# EARM01_Rev_B.net
KiCad netlist of a schematic drawn in EAGLE
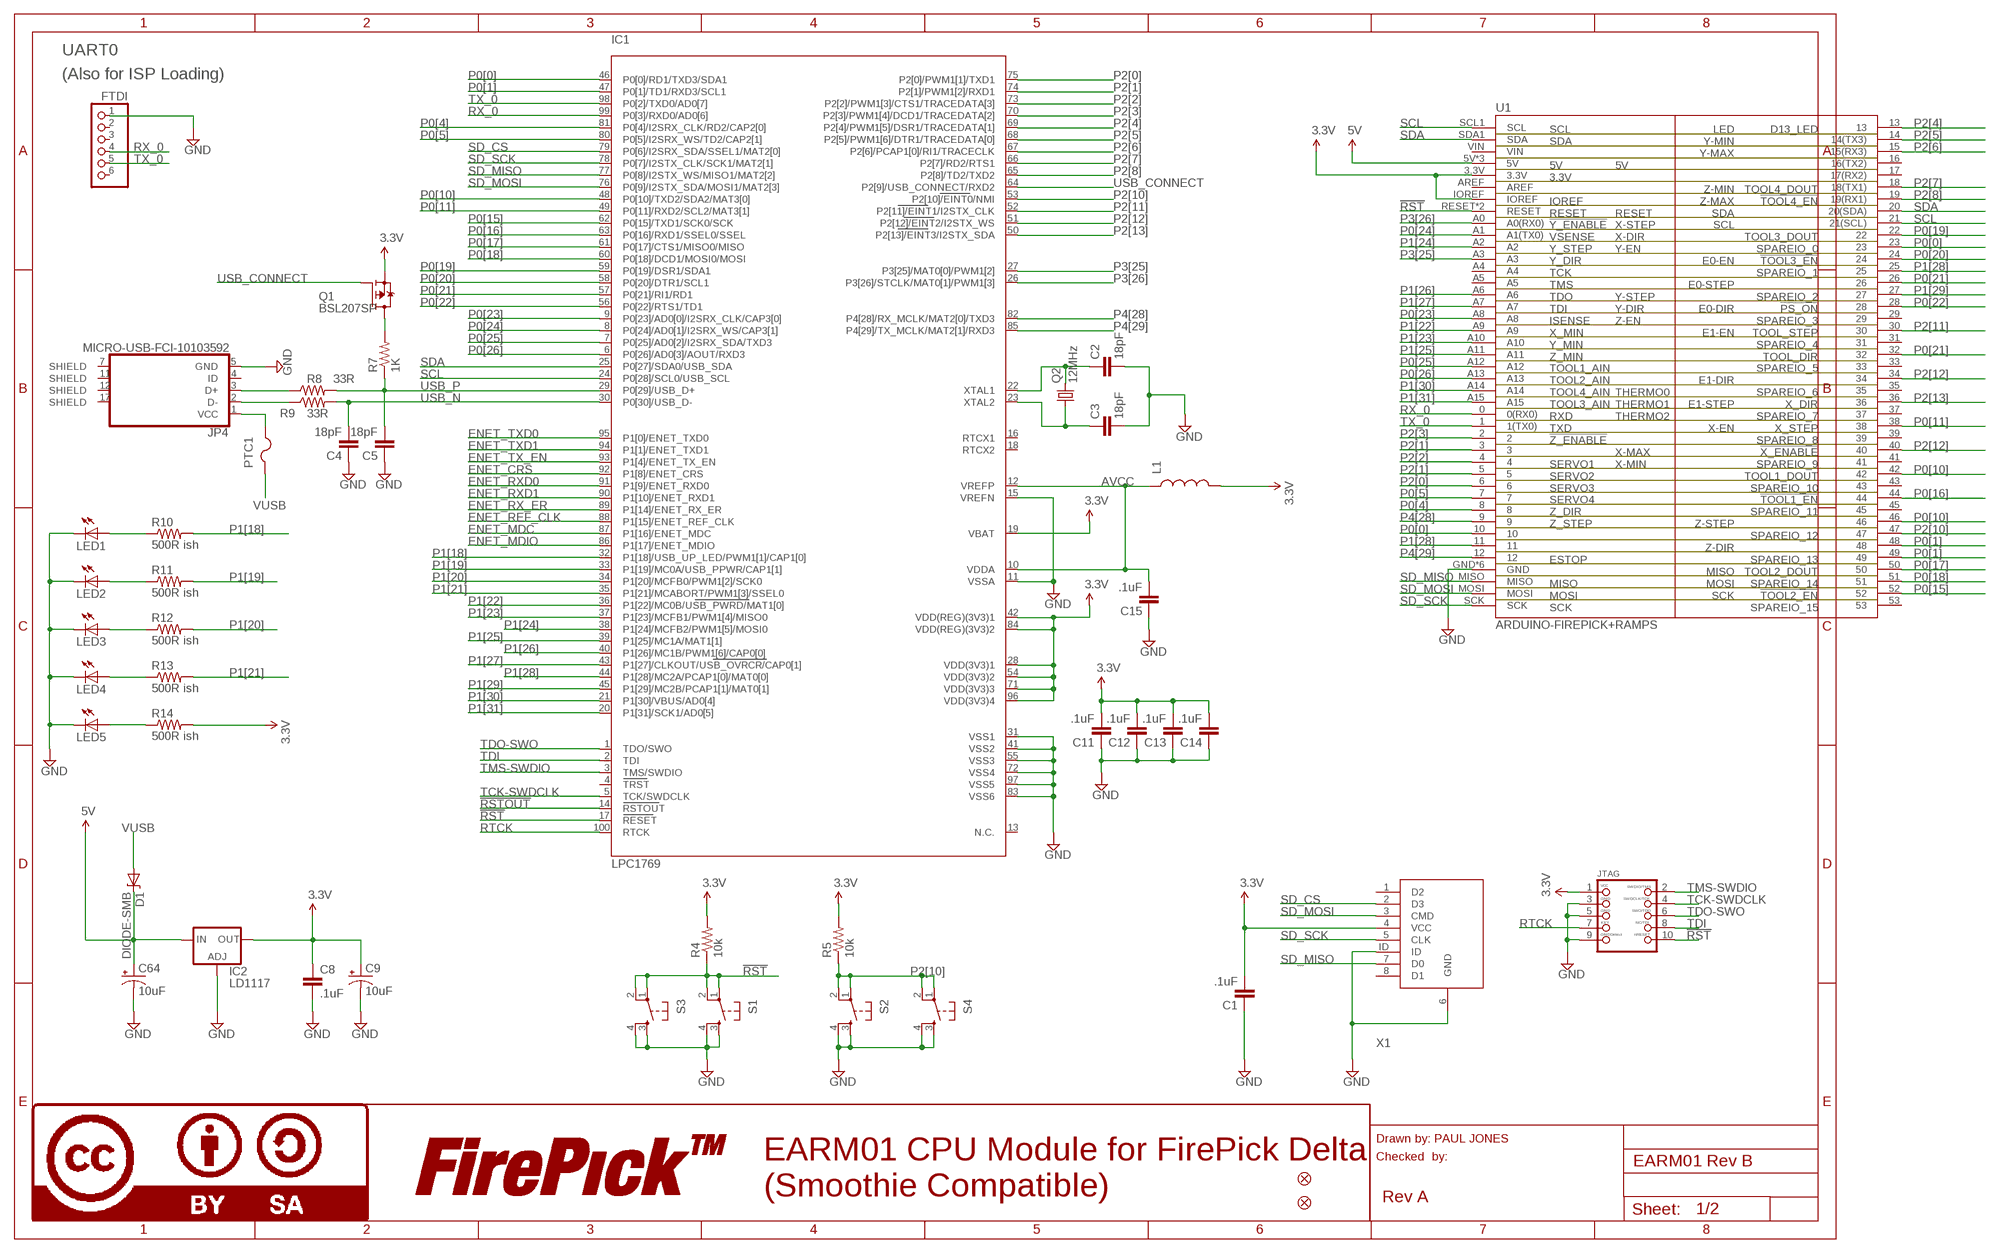
[diagram p0: schematic, sheet 1]
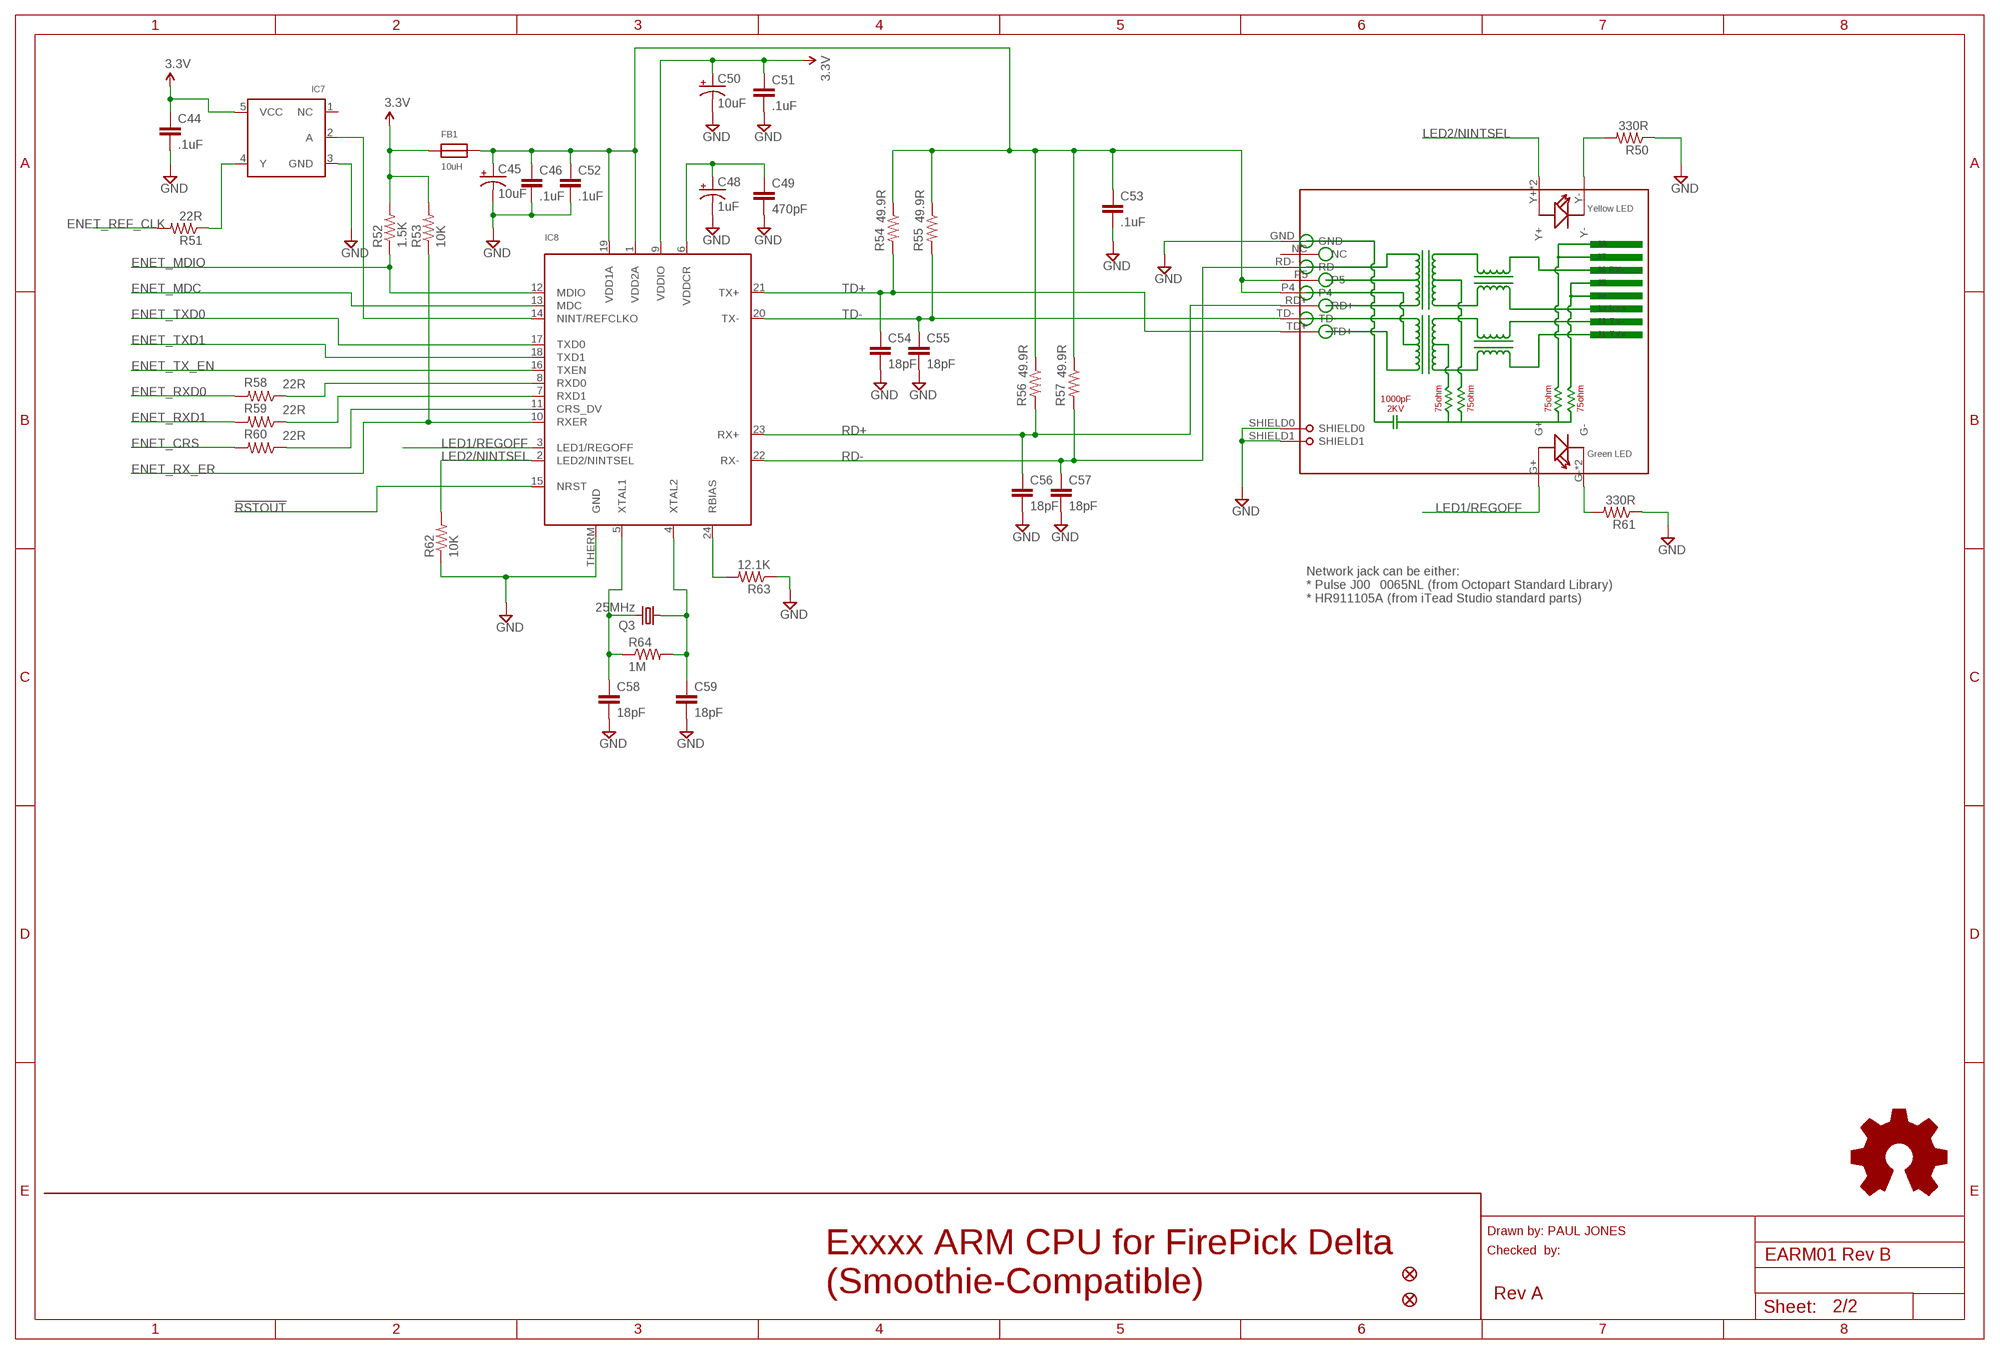
[diagram p1: schematic, sheet 2]

(export (version "E")
  (design (tool "Eeschema 10.0.6"))
  (components
    (comp (ref "C44")
      (value ".1uF")
      (footprint "eagle-import:C0603")
      (libsource (lib "eagle-import") (part "resistor_C-EUC0603"))
    )
    (comp (ref "C45")
      (value "10uF")
      (footprint "eagle-import:EIA3216")
      (libsource (lib "eagle-import") (part "CAP_POL1206"))
    )
    (comp (ref "C46")
      (value ".1uF")
      (footprint "eagle-import:C0603")
      (libsource (lib "eagle-import") (part "resistor_C-EUC0603"))
    )
    (comp (ref "C48")
      (value "1uF")
      (footprint "eagle-import:EIA3216")
      (libsource (lib "eagle-import") (part "CAP_POL1206"))
    )
    (comp (ref "C49")
      (value "470pF")
      (footprint "eagle-import:C0603K")
      (libsource (lib "eagle-import") (part "resistor_C-EUC0603K"))
    )
    (comp (ref "C50")
      (value "10uF")
      (footprint "eagle-import:EIA3216")
      (libsource (lib "eagle-import") (part "CAP_POL1206"))
    )
    (comp (ref "C51")
      (value ".1uF")
      (footprint "eagle-import:C0603")
      (libsource (lib "eagle-import") (part "resistor_C-EUC0603"))
    )
    (comp (ref "C52")
      (value ".1uF")
      (footprint "eagle-import:C0603")
      (libsource (lib "eagle-import") (part "resistor_C-EUC0603"))
    )
    (comp (ref "C53")
      (value ".1uF")
      (footprint "eagle-import:C0603")
      (libsource (lib "eagle-import") (part "resistor_C-EUC0603"))
    )
    (comp (ref "C54")
      (value "18pF")
      (footprint "eagle-import:C0603")
      (libsource (lib "eagle-import") (part "resistor_C-EUC0603"))
    )
    (comp (ref "C55")
      (value "18pF")
      (footprint "eagle-import:C0603")
      (libsource (lib "eagle-import") (part "resistor_C-EUC0603"))
    )
    (comp (ref "C56")
      (value "18pF")
      (footprint "eagle-import:C0603")
      (libsource (lib "eagle-import") (part "resistor_C-EUC0603"))
    )
    (comp (ref "C57")
      (value "18pF")
      (footprint "eagle-import:C0603")
      (libsource (lib "eagle-import") (part "resistor_C-EUC0603"))
    )
    (comp (ref "C58")
      (value "18pF")
      (footprint "eagle-import:C0603")
      (libsource (lib "eagle-import") (part "resistor_C-EUC0603"))
    )
    (comp (ref "C59")
      (value "18pF")
      (footprint "eagle-import:C0603")
      (libsource (lib "eagle-import") (part "resistor_C-EUC0603"))
    )
    (comp (ref "FB1")
      (value "10uH")
      (footprint "eagle-import:0603")
      (libsource (lib "eagle-import") (part "FERRITE"))
    )
    (comp (ref "FID17")
      (value "FIDUCIAL1X2")
      (footprint "eagle-import:FIDUCIAL-1X2")
      (libsource (lib "eagle-import") (part "FIDUCIAL1X2"))
    )
    (comp (ref "FID18")
      (value "FIDUCIAL1X2")
      (footprint "eagle-import:FIDUCIAL-1X2")
      (libsource (lib "eagle-import") (part "FIDUCIAL1X2"))
    )
    (comp (ref "IC7")
      (value "74LVC1G04")
      (footprint "eagle-import:SOT23-5")
      (libsource (lib "eagle-import") (part "74LVC1G04"))
    )
    (comp (ref "IC8")
      (value "LAN8720")
      (footprint "eagle-import:QFN24_4MM")
      (libsource (lib "eagle-import") (part "LAN8720"))
    )
    (comp (ref "LOGO10")
      (value "LOGO-OSHWSMALL")
      (footprint "eagle-import:LOGO-OSHW-SMALL")
      (libsource (lib "eagle-import") (part "LOGO-OSHWSMALL"))
    )
    (comp (ref "Q3")
      (value "25MHz")
      (footprint "eagle-import:HC49UP")
      (libsource (lib "eagle-import") (part "CRYSTALHC49UP"))
    )
    (comp (ref "R50")
      (value "330R")
      (footprint "eagle-import:R0603")
      (libsource (lib "eagle-import") (part "R-US_R0603"))
    )
    (comp (ref "R51")
      (value "22R")
      (footprint "eagle-import:R0603")
      (libsource (lib "eagle-import") (part "R-US_R0603"))
    )
    (comp (ref "R52")
      (value "1.5K")
      (footprint "eagle-import:R0603")
      (libsource (lib "eagle-import") (part "R-US_R0603"))
    )
    (comp (ref "R53")
      (value "10K")
      (footprint "eagle-import:R0603")
      (libsource (lib "eagle-import") (part "R-US_R0603"))
    )
    (comp (ref "R54")
      (value "49.9R")
      (footprint "eagle-import:R0603")
      (libsource (lib "eagle-import") (part "R-US_R0603"))
    )
    (comp (ref "R55")
      (value "49.9R")
      (footprint "eagle-import:R0603")
      (libsource (lib "eagle-import") (part "R-US_R0603"))
    )
    (comp (ref "R56")
      (value "49.9R")
      (footprint "eagle-import:R0603")
      (libsource (lib "eagle-import") (part "R-US_R0603"))
    )
    (comp (ref "R57")
      (value "49.9R")
      (footprint "eagle-import:R0603")
      (libsource (lib "eagle-import") (part "R-US_R0603"))
    )
    (comp (ref "R58")
      (value "22R")
      (footprint "eagle-import:R0603")
      (libsource (lib "eagle-import") (part "R-US_R0603"))
    )
    (comp (ref "R59")
      (value "22R")
      (footprint "eagle-import:R0603")
      (libsource (lib "eagle-import") (part "R-US_R0603"))
    )
    (comp (ref "R60")
      (value "22R")
      (footprint "eagle-import:R0603")
      (libsource (lib "eagle-import") (part "R-US_R0603"))
    )
    (comp (ref "R61")
      (value "330R")
      (footprint "eagle-import:R0603")
      (libsource (lib "eagle-import") (part "R-US_R0603"))
    )
    (comp (ref "R62")
      (value "10K")
      (footprint "eagle-import:R0603")
      (libsource (lib "eagle-import") (part "R-US_R0603"))
    )
    (comp (ref "R63")
      (value "12.1K")
      (footprint "eagle-import:R0603")
      (libsource (lib "eagle-import") (part "R-US_R0603"))
    )
    (comp (ref "R64")
      (value "1M")
      (footprint "eagle-import:R0603")
      (libsource (lib "eagle-import") (part "R-US_R0603"))
    )
    (comp (ref "RJ1")
      (value "HR911105A")
      (footprint "eagle-import:HR911105A")
      (libsource (lib "eagle-import") (part "HR911105A"))
    )
    (comp (ref "C1")
      (value ".1uF")
      (footprint "eagle-import:C0603")
      (libsource (lib "eagle-import") (part "resistor_C-EUC0603"))
    )
    (comp (ref "C2")
      (value "18pF")
      (footprint "eagle-import:C0603")
      (libsource (lib "eagle-import") (part "C-EUC0603"))
    )
    (comp (ref "C3")
      (value "18pF")
      (footprint "eagle-import:C0603")
      (libsource (lib "eagle-import") (part "C-EUC0603"))
    )
    (comp (ref "C4")
      (value "18pF")
      (footprint "eagle-import:C0603")
      (libsource (lib "eagle-import") (part "C-EUC0603"))
    )
    (comp (ref "C5")
      (value "18pF")
      (footprint "eagle-import:C0603")
      (libsource (lib "eagle-import") (part "C-EUC0603"))
    )
    (comp (ref "C8")
      (value ".1uF")
      (footprint "eagle-import:C0603")
      (libsource (lib "eagle-import") (part "C-EUC0603"))
    )
    (comp (ref "C9")
      (value "10uF")
      (footprint "eagle-import:EIA3216")
      (libsource (lib "eagle-import") (part "CAP_POL1206"))
    )
    (comp (ref "C11")
      (value ".1uF")
      (footprint "eagle-import:C0603")
      (libsource (lib "eagle-import") (part "C-EUC0603"))
    )
    (comp (ref "C12")
      (value ".1uF")
      (footprint "eagle-import:C0603")
      (libsource (lib "eagle-import") (part "C-EUC0603"))
    )
    (comp (ref "C13")
      (value ".1uF")
      (footprint "eagle-import:C0603")
      (libsource (lib "eagle-import") (part "C-EUC0603"))
    )
    (comp (ref "C14")
      (value ".1uF")
      (footprint "eagle-import:C0603")
      (libsource (lib "eagle-import") (part "C-EUC0603"))
    )
    (comp (ref "C15")
      (value ".1uF")
      (footprint "eagle-import:C0603")
      (libsource (lib "eagle-import") (part "resistor_C-EUC0603"))
    )
    (comp (ref "C64")
      (value "10uF")
      (footprint "eagle-import:EIA3216")
      (libsource (lib "eagle-import") (part "CAP_POL1206"))
    )
    (comp (ref "D1")
      (value "DIODE-SMB")
      (footprint "eagle-import:SMB")
      (libsource (lib "eagle-import") (part "DIODE-ZENER"))
    )
    (comp (ref "FID5")
      (value "FIDUCIAL1X2")
      (footprint "eagle-import:FIDUCIAL-1X2")
      (libsource (lib "eagle-import") (part "FIDUCIAL1X2"))
    )
    (comp (ref "FID6")
      (value "FIDUCIAL1X2")
      (footprint "eagle-import:FIDUCIAL-1X2")
      (libsource (lib "eagle-import") (part "FIDUCIAL1X2"))
    )
    (comp (ref "FTDI")
      (value "PINHD-1X6")
      (footprint "eagle-import:1X06")
      (libsource (lib "eagle-import") (part "PINHD-1X6"))
    )
    (comp (ref "IC1")
      (value "LPC1769")
      (footprint "eagle-import:LQFP100")
      (libsource (lib "eagle-import") (part "LPC1768"))
    )
    (comp (ref "IC2")
      (value "LD1117")
      (footprint "eagle-import:SOT223")
      (libsource (lib "eagle-import") (part "LD117A?S12TR"))
    )
    (comp (ref "JP4")
      (value "MICRO-USB-FCI-10103592")
      (footprint "eagle-import:MICRO-USB-FCI-10103592")
      (libsource (lib "eagle-import") (part "MICRO-USB-FCI-10103592"))
    )
    (comp (ref "JTAG")
      (value "JTAG-CORTEXM3")
      (footprint "eagle-import:2X05_1.27MM_SMT")
      (libsource (lib "eagle-import") (part "JTAG-CORTEXM3"))
    )
    (comp (ref "L1")
      (value "INDUCTOR0603")
      (footprint "eagle-import:0603")
      (libsource (lib "eagle-import") (part "INDUCTOR0603"))
    )
    (comp (ref "LED1")
      (value "LED")
      (footprint "eagle-import:LED-1206-BOTTOM")
      (libsource (lib "eagle-import") (part "LED"))
    )
    (comp (ref "LED2")
      (value "LED")
      (footprint "eagle-import:LED-1206-BOTTOM")
      (libsource (lib "eagle-import") (part "LED"))
    )
    (comp (ref "LED3")
      (value "LED")
      (footprint "eagle-import:LED-1206-BOTTOM")
      (libsource (lib "eagle-import") (part "LED"))
    )
    (comp (ref "LED4")
      (value "LED")
      (footprint "eagle-import:LED-1206-BOTTOM")
      (libsource (lib "eagle-import") (part "LED"))
    )
    (comp (ref "LED5")
      (value "LED")
      (footprint "eagle-import:LED-1206-BOTTOM")
      (libsource (lib "eagle-import") (part "LED"))
    )
    (comp (ref "LOGO4")
      (value "LOGO-FIREPICKMEDIUM")
      (footprint "eagle-import:LOGO-FIREPICK-MEDIUM")
      (libsource (lib "eagle-import") (part "LOGO-FIREPICKMEDIUM"))
    )
    (comp (ref "LOGO6")
      (value "LOGO-CC-BY-SAMEDIUM")
      (footprint "eagle-import:LOGO-CC-BY-SA-MEDIUM")
      (libsource (lib "eagle-import") (part "LOGO-CC-BY-SAMEDIUM"))
    )
    (comp (ref "PTC1")
      (value "PTCFUSE-1812")
      (footprint "eagle-import:1812")
      (libsource (lib "eagle-import") (part "PTCFUSE-1812"))
    )
    (comp (ref "Q1")
      (value "BSL207SP")
      (footprint "eagle-import:SC74_INFINEON")
      (libsource (lib "eagle-import") (part "BSL207SP"))
    )
    (comp (ref "Q2")
      (value "12MHz")
      (footprint "eagle-import:HC49UP")
      (libsource (lib "eagle-import") (part "CRYSTALHC49UP"))
    )
    (comp (ref "R4")
      (value "10k")
      (footprint "eagle-import:R0603")
      (libsource (lib "eagle-import") (part "R-US_R0603"))
    )
    (comp (ref "R5")
      (value "10k")
      (footprint "eagle-import:R0603")
      (libsource (lib "eagle-import") (part "R-US_R0603"))
    )
    (comp (ref "R7")
      (value "1K")
      (footprint "eagle-import:R0603")
      (libsource (lib "eagle-import") (part "R-US_R0603"))
    )
    (comp (ref "R8")
      (value "33R")
      (footprint "eagle-import:R0603")
      (libsource (lib "eagle-import") (part "R-US_R0603"))
    )
    (comp (ref "R9")
      (value "33R")
      (footprint "eagle-import:R0603")
      (libsource (lib "eagle-import") (part "R-US_R0603"))
    )
    (comp (ref "R10")
      (value "500R ish")
      (footprint "eagle-import:R0603")
      (libsource (lib "eagle-import") (part "R-US_R0603"))
    )
    (comp (ref "R11")
      (value "500R ish")
      (footprint "eagle-import:R0603")
      (libsource (lib "eagle-import") (part "R-US_R0603"))
    )
    (comp (ref "R12")
      (value "500R ish")
      (footprint "eagle-import:R0603")
      (libsource (lib "eagle-import") (part "R-US_R0603"))
    )
    (comp (ref "R13")
      (value "500R ish")
      (footprint "eagle-import:R0603")
      (libsource (lib "eagle-import") (part "R-US_R0603"))
    )
    (comp (ref "R14")
      (value "500R ish")
      (footprint "eagle-import:R0603")
      (libsource (lib "eagle-import") (part "R-US_R0603"))
    )
    (comp (ref "S1")
      (value "TAC_SWITCHSMD")
      (footprint "eagle-import:TACTILE_SWITCH_SMD")
      (libsource (lib "eagle-import") (part "TAC_SWITCHSMD"))
    )
    (comp (ref "S2")
      (value "TAC_SWITCHSMD")
      (footprint "eagle-import:TACTILE_SWITCH_SMD")
      (libsource (lib "eagle-import") (part "TAC_SWITCHSMD"))
    )
    (comp (ref "S3")
      (value "TAC_SWITCHSMD")
      (footprint "eagle-import:TACTILE_SWITCH_SMD")
      (libsource (lib "eagle-import") (part "TAC_SWITCHSMD"))
    )
    (comp (ref "S4")
      (value "TAC_SWITCHSMD")
      (footprint "eagle-import:TACTILE_SWITCH_SMD")
      (libsource (lib "eagle-import") (part "TAC_SWITCHSMD"))
    )
    (comp (ref "U1")
      (value "ARDUINO-FIREPICK+RAMPS")
      (footprint "eagle-import:ARDUINO_MEGA_NEW")
      (libsource (lib "eagle-import") (part "ARDUINO-FIREPICK+RAMPS"))
    )
    (comp (ref "X1")
      (value "ST9S008V4AR1500")
      (footprint "eagle-import:ST9S008V4AR1500")
      (libsource (lib "eagle-import") (part "ST9S008V4AR1500"))
    )
  )
  (nets
    (net (code "1") (name "3.3V") (class "Default")
      (node (ref "C1") (pin "2") (pinfunction "2_2") (pintype "passive"))
      (node (ref "C11") (pin "2") (pinfunction "2_2") (pintype "passive"))
      (node (ref "C12") (pin "2") (pinfunction "2_2") (pintype "passive"))
      (node (ref "C13") (pin "2") (pinfunction "2_2") (pintype "passive"))
      (node (ref "C14") (pin "2") (pinfunction "2_2") (pintype "passive"))
      (node (ref "C44") (pin "1") (pinfunction "1_1") (pintype "passive"))
      (node (ref "C50") (pin "A") (pinfunction "+_A") (pintype "passive"))
      (node (ref "C51") (pin "1") (pinfunction "1_1") (pintype "passive"))
      (node (ref "C8") (pin "1") (pinfunction "1_1") (pintype "passive"))
      (node (ref "C9") (pin "A") (pinfunction "+_A") (pintype "passive"))
      (node (ref "FB1") (pin "1") (pinfunction "P$1_1") (pintype "bidirectional"))
      (node (ref "IC1") (pin "19") (pinfunction "VBAT_19") (pintype "bidirectional"))
      (node (ref "IC1") (pin "28") (pinfunction "VDD(3V3)1_28") (pintype "bidirectional"))
      (node (ref "IC1") (pin "42") (pinfunction "VDD(REG)(3V3)1_42") (pintype "bidirectional"))
      (node (ref "IC1") (pin "54") (pinfunction "VDD(3V3)2_54") (pintype "bidirectional"))
      (node (ref "IC1") (pin "71") (pinfunction "VDD(3V3)3_71") (pintype "bidirectional"))
      (node (ref "IC1") (pin "84") (pinfunction "VDD(REG)(3V3)2_84") (pintype "bidirectional"))
      (node (ref "IC1") (pin "96") (pinfunction "VDD(3V3)4_96") (pintype "bidirectional"))
      (node (ref "IC2") (pin "4") (pinfunction "OUT_4") (pintype "passive"))
      (node (ref "IC7") (pin "5") (pinfunction "VCC_5") (pintype "power_in"))
      (node (ref "IC8") (pin "9") (pinfunction "VDDIO_9") (pintype "bidirectional"))
      (node (ref "JTAG") (pin "1") (pinfunction "1_1") (pintype "passive"))
      (node (ref "L1") (pin "2") (pinfunction "2_2") (pintype "passive"))
      (node (ref "Q1") (pin "4") (pinfunction "S_4") (pintype "passive"))
      (node (ref "R14") (pin "2") (pinfunction "2_2") (pintype "passive"))
      (node (ref "R4") (pin "2") (pinfunction "2_2") (pintype "passive"))
      (node (ref "R5") (pin "2") (pinfunction "2_2") (pintype "passive"))
      (node (ref "R52") (pin "2") (pinfunction "2_2") (pintype "passive"))
      (node (ref "R53") (pin "2") (pinfunction "2_2") (pintype "passive"))
      (node (ref "U1") (pin "3.3V") (pinfunction "3.3V_3.3V") (pintype "bidirectional"))
      (node (ref "U1") (pin "IOREF") (pinfunction "IOREF_IOREF") (pintype "bidirectional"))
      (node (ref "X1") (pin "4") (pinfunction "VCC_4") (pintype "input"))
    )
    (net (code "2") (name "5V") (class "Default")
      (node (ref "C64") (pin "A") (pinfunction "+_A") (pintype "passive"))
      (node (ref "D1") (pin "C") (pinfunction "C_C") (pintype "passive"))
      (node (ref "IC2") (pin "3") (pinfunction "IN_3") (pintype "input"))
      (node (ref "U1") (pin "5V") (pinfunction "5V_5V") (pintype "bidirectional"))
      (node (ref "U1") (pin "5V@1") (pinfunction "5V_5V@1") (pintype "bidirectional"))
      (node (ref "U1") (pin "5V@2") (pinfunction "5V_5V@2") (pintype "bidirectional"))
    )
    (net (code "3") (name "AVCC") (class "Default")
      (node (ref "C15") (pin "2") (pinfunction "2_2") (pintype "passive"))
      (node (ref "IC1") (pin "10") (pinfunction "VDDA_10") (pintype "bidirectional"))
      (node (ref "IC1") (pin "12") (pinfunction "VREFP_12") (pintype "bidirectional"))
      (node (ref "L1") (pin "1") (pinfunction "1_1") (pintype "passive"))
    )
    (net (code "4") (name "ENET_CRS") (class "Default")
      (node (ref "IC1") (pin "92") (pinfunction "P1[8]/ENET_CRS_92") (pintype "bidirectional"))
      (node (ref "R60") (pin "2") (pinfunction "2_2") (pintype "passive"))
    )
    (net (code "5") (name "ENET_MDC") (class "Default")
      (node (ref "IC1") (pin "87") (pinfunction "P1[16]/ENET_MDC_87") (pintype "bidirectional"))
      (node (ref "IC8") (pin "13") (pinfunction "MDC_13") (pintype "bidirectional"))
    )
    (net (code "6") (name "ENET_MDIO") (class "Default")
      (node (ref "IC1") (pin "86") (pinfunction "P1[17]/ENET_MDIO_86") (pintype "bidirectional"))
      (node (ref "IC8") (pin "12") (pinfunction "MDIO_12") (pintype "bidirectional"))
      (node (ref "R52") (pin "1") (pinfunction "1_1") (pintype "passive"))
    )
    (net (code "7") (name "ENET_REF_CLK") (class "Default")
      (node (ref "IC1") (pin "88") (pinfunction "P1[15]/ENET_REF_CLK_88") (pintype "bidirectional"))
      (node (ref "R51") (pin "2") (pinfunction "2_2") (pintype "passive"))
    )
    (net (code "8") (name "ENET_RXD0") (class "Default")
      (node (ref "IC1") (pin "91") (pinfunction "P1[9]/ENET_RXD0_91") (pintype "bidirectional"))
      (node (ref "R58") (pin "2") (pinfunction "2_2") (pintype "passive"))
    )
    (net (code "9") (name "ENET_RXD1") (class "Default")
      (node (ref "IC1") (pin "90") (pinfunction "P1[10]/ENET_RXD1_90") (pintype "bidirectional"))
      (node (ref "R59") (pin "2") (pinfunction "2_2") (pintype "passive"))
    )
    (net (code "10") (name "ENET_RX_ER") (class "Default")
      (node (ref "IC1") (pin "89") (pinfunction "P1[14]/ENET_RX_ER_89") (pintype "bidirectional"))
      (node (ref "IC8") (pin "10") (pinfunction "RXER_10") (pintype "bidirectional"))
      (node (ref "R53") (pin "1") (pinfunction "1_1") (pintype "passive"))
    )
    (net (code "11") (name "ENET_TXD0") (class "Default")
      (node (ref "IC1") (pin "95") (pinfunction "P1[0]/ENET_TXD0_95") (pintype "bidirectional"))
      (node (ref "IC8") (pin "17") (pinfunction "TXD0_17") (pintype "bidirectional"))
    )
    (net (code "12") (name "ENET_TXD1") (class "Default")
      (node (ref "IC1") (pin "94") (pinfunction "P1[1]/ENET_TXD1_94") (pintype "bidirectional"))
      (node (ref "IC8") (pin "18") (pinfunction "TXD1_18") (pintype "bidirectional"))
    )
    (net (code "13") (name "ENET_TX_EN") (class "Default")
      (node (ref "IC1") (pin "93") (pinfunction "P1[4]/ENET_TX_EN_93") (pintype "bidirectional"))
      (node (ref "IC8") (pin "16") (pinfunction "TXEN_16") (pintype "bidirectional"))
    )
    (net (code "14") (name "GND") (class "Default")
      (node (ref "C1") (pin "1") (pinfunction "1_1") (pintype "passive"))
      (node (ref "C11") (pin "1") (pinfunction "1_1") (pintype "passive"))
      (node (ref "C12") (pin "1") (pinfunction "1_1") (pintype "passive"))
      (node (ref "C13") (pin "1") (pinfunction "1_1") (pintype "passive"))
      (node (ref "C14") (pin "1") (pinfunction "1_1") (pintype "passive"))
      (node (ref "C15") (pin "1") (pinfunction "1_1") (pintype "passive"))
      (node (ref "C2") (pin "2") (pinfunction "2_2") (pintype "passive"))
      (node (ref "C3") (pin "2") (pinfunction "2_2") (pintype "passive"))
      (node (ref "C4") (pin "1") (pinfunction "1_1") (pintype "passive"))
      (node (ref "C44") (pin "2") (pinfunction "2_2") (pintype "passive"))
      (node (ref "C45") (pin "C") (pinfunction "-_C") (pintype "passive"))
      (node (ref "C46") (pin "2") (pinfunction "2_2") (pintype "passive"))
      (node (ref "C48") (pin "C") (pinfunction "-_C") (pintype "passive"))
      (node (ref "C49") (pin "2") (pinfunction "2_2") (pintype "passive"))
      (node (ref "C5") (pin "1") (pinfunction "1_1") (pintype "passive"))
      (node (ref "C50") (pin "C") (pinfunction "-_C") (pintype "passive"))
      (node (ref "C51") (pin "2") (pinfunction "2_2") (pintype "passive"))
      (node (ref "C52") (pin "2") (pinfunction "2_2") (pintype "passive"))
      (node (ref "C53") (pin "2") (pinfunction "2_2") (pintype "passive"))
      (node (ref "C54") (pin "2") (pinfunction "2_2") (pintype "passive"))
      (node (ref "C55") (pin "2") (pinfunction "2_2") (pintype "passive"))
      (node (ref "C56") (pin "2") (pinfunction "2_2") (pintype "passive"))
      (node (ref "C57") (pin "2") (pinfunction "2_2") (pintype "passive"))
      (node (ref "C58") (pin "2") (pinfunction "2_2") (pintype "passive"))
      (node (ref "C59") (pin "2") (pinfunction "2_2") (pintype "passive"))
      (node (ref "C64") (pin "C") (pinfunction "-_C") (pintype "passive"))
      (node (ref "C8") (pin "2") (pinfunction "2_2") (pintype "passive"))
      (node (ref "C9") (pin "C") (pinfunction "-_C") (pintype "passive"))
      (node (ref "FTDI") (pin "1") (pinfunction "1_1") (pintype "passive"))
      (node (ref "IC1") (pin "11") (pinfunction "VSSA_11") (pintype "bidirectional"))
      (node (ref "IC1") (pin "15") (pinfunction "VREFN_15") (pintype "bidirectional"))
      (node (ref "IC1") (pin "31") (pinfunction "VSS1_31") (pintype "bidirectional"))
      (node (ref "IC1") (pin "41") (pinfunction "VSS2_41") (pintype "bidirectional"))
      (node (ref "IC1") (pin "55") (pinfunction "VSS3_55") (pintype "bidirectional"))
      (node (ref "IC1") (pin "72") (pinfunction "VSS4_72") (pintype "bidirectional"))
      (node (ref "IC1") (pin "83") (pinfunction "VSS6_83") (pintype "bidirectional"))
      (node (ref "IC1") (pin "97") (pinfunction "VSS5_97") (pintype "bidirectional"))
      (node (ref "IC2") (pin "1") (pinfunction "ADJ_1") (pintype "input"))
      (node (ref "IC7") (pin "3") (pinfunction "GND_3") (pintype "power_in"))
      (node (ref "IC8") (pin "THERM") (pinfunction "GND_THERM") (pintype "bidirectional"))
      (node (ref "JP4") (pin "5") (pinfunction "GND_5") (pintype "bidirectional"))
      (node (ref "JTAG") (pin "3") (pinfunction "3_3") (pintype "passive"))
      (node (ref "JTAG") (pin "5") (pinfunction "5_5") (pintype "passive"))
      (node (ref "JTAG") (pin "9") (pinfunction "9_9") (pintype "passive"))
      (node (ref "LED1") (pin "C") (pinfunction "C_C") (pintype "passive"))
      (node (ref "LED2") (pin "C") (pinfunction "C_C") (pintype "passive"))
      (node (ref "LED3") (pin "C") (pinfunction "C_C") (pintype "passive"))
      (node (ref "LED4") (pin "C") (pinfunction "C_C") (pintype "passive"))
      (node (ref "LED5") (pin "C") (pinfunction "C_C") (pintype "passive"))
      (node (ref "R50") (pin "1") (pinfunction "1_1") (pintype "passive"))
      (node (ref "R61") (pin "1") (pinfunction "1_1") (pintype "passive"))
      (node (ref "R62") (pin "1") (pinfunction "1_1") (pintype "passive"))
      (node (ref "R63") (pin "1") (pinfunction "1_1") (pintype "passive"))
      (node (ref "RJ1") (pin "GND") (pinfunction "GND_GND") (pintype "bidirectional"))
      (node (ref "RJ1") (pin "SHIELD0") (pinfunction "SHIELD0_SHIELD0") (pintype "bidirectional"))
      (node (ref "RJ1") (pin "SHIELD1") (pinfunction "SHIELD1_SHIELD1") (pintype "bidirectional"))
      (node (ref "S1") (pin "3") (pinfunction "3_3") (pintype "passive"))
      (node (ref "S1") (pin "4") (pinfunction "4_4") (pintype "passive"))
      (node (ref "S2") (pin "3") (pinfunction "3_3") (pintype "passive"))
      (node (ref "S2") (pin "4") (pinfunction "4_4") (pintype "passive"))
      (node (ref "S3") (pin "3") (pinfunction "3_3") (pintype "passive"))
      (node (ref "S3") (pin "4") (pinfunction "4_4") (pintype "passive"))
      (node (ref "S4") (pin "3") (pinfunction "3_3") (pintype "passive"))
      (node (ref "S4") (pin "4") (pinfunction "4_4") (pintype "passive"))
      (node (ref "U1") (pin "GND") (pinfunction "GND_GND") (pintype "bidirectional"))
      (node (ref "U1") (pin "GND@0") (pinfunction "GND_GND@0") (pintype "bidirectional"))
      (node (ref "U1") (pin "GND@1") (pinfunction "GND_GND@1") (pintype "bidirectional"))
      (node (ref "U1") (pin "GND@2") (pinfunction "GND_GND@2") (pintype "bidirectional"))
      (node (ref "U1") (pin "GND@3") (pinfunction "GND_GND@3") (pintype "bidirectional"))
      (node (ref "U1") (pin "GNDI") (pinfunction "GND_GNDI") (pintype "bidirectional"))
      (node (ref "X1") (pin "6") (pinfunction "GND_6") (pintype "passive"))
      (node (ref "X1") (pin "ID") (pinfunction "ID_ID") (pintype "passive"))
    )
    (net (code "15") (name "LED1{slash}REGOFF") (class "Default")
      (node (ref "IC8") (pin "3") (pinfunction "LED1/REGOFF_3") (pintype "bidirectional"))
      (node (ref "RJ1") (pin "G+") (pinfunction "G+_G+") (pintype "bidirectional"))
    )
    (net (code "16") (name "LED2{slash}NINTSEL") (class "Default")
      (node (ref "IC8") (pin "2") (pinfunction "LED2/NINTSEL_2") (pintype "bidirectional"))
      (node (ref "R62") (pin "2") (pinfunction "2_2") (pintype "passive"))
      (node (ref "RJ1") (pin "Y+") (pinfunction "Y+_Y+") (pintype "bidirectional"))
      (node (ref "RJ1") (pin "Y++") (pinfunction "Y+_Y++") (pintype "bidirectional"))
    )
    (net (code "17") (name "Net-(C45-+)") (class "Default")
      (node (ref "C45") (pin "A") (pinfunction "+_A") (pintype "passive"))
      (node (ref "C46") (pin "1") (pinfunction "1_1") (pintype "passive"))
      (node (ref "C52") (pin "1") (pinfunction "1_1") (pintype "passive"))
      (node (ref "C53") (pin "1") (pinfunction "1_1") (pintype "passive"))
      (node (ref "FB1") (pin "2") (pinfunction "P$2_2") (pintype "bidirectional"))
      (node (ref "IC8") (pin "1") (pinfunction "VDD2A_1") (pintype "bidirectional"))
      (node (ref "IC8") (pin "19") (pinfunction "VDD1A_19") (pintype "bidirectional"))
      (node (ref "R54") (pin "1") (pinfunction "1_1") (pintype "passive"))
      (node (ref "R55") (pin "1") (pinfunction "1_1") (pintype "passive"))
      (node (ref "R56") (pin "1") (pinfunction "1_1") (pintype "passive"))
      (node (ref "R57") (pin "1") (pinfunction "1_1") (pintype "passive"))
      (node (ref "RJ1") (pin "P4") (pinfunction "P4_P4") (pintype "bidirectional"))
      (node (ref "RJ1") (pin "P5") (pinfunction "P5_P5") (pintype "bidirectional"))
    )
    (net (code "18") (name "Net-(C48-+)") (class "Default")
      (node (ref "C48") (pin "A") (pinfunction "+_A") (pintype "passive"))
      (node (ref "C49") (pin "1") (pinfunction "1_1") (pintype "passive"))
      (node (ref "IC8") (pin "6") (pinfunction "VDDCR_6") (pintype "bidirectional"))
    )
    (net (code "19") (name "Net-(IC1-XTAL1)") (class "Default")
      (node (ref "C2") (pin "1") (pinfunction "1_1") (pintype "passive"))
      (node (ref "IC1") (pin "22") (pinfunction "XTAL1_22") (pintype "bidirectional"))
      (node (ref "Q2") (pin "2") (pinfunction "2_2") (pintype "passive"))
    )
    (net (code "20") (name "Net-(IC1-XTAL2)") (class "Default")
      (node (ref "C3") (pin "1") (pinfunction "1_1") (pintype "passive"))
      (node (ref "IC1") (pin "23") (pinfunction "XTAL2_23") (pintype "bidirectional"))
      (node (ref "Q2") (pin "1") (pinfunction "1_1") (pintype "passive"))
    )
    (net (code "21") (name "Net-(IC7-A)") (class "Default")
      (node (ref "IC7") (pin "2") (pinfunction "A_2") (pintype "bidirectional"))
      (node (ref "IC8") (pin "14") (pinfunction "NINT/REFCLKO_14") (pintype "bidirectional"))
    )
    (net (code "22") (name "Net-(IC7-Y)") (class "Default")
      (node (ref "IC7") (pin "4") (pinfunction "Y_4") (pintype "bidirectional"))
      (node (ref "R51") (pin "1") (pinfunction "1_1") (pintype "passive"))
    )
    (net (code "23") (name "Net-(IC8-CRS_DV)") (class "Default")
      (node (ref "IC8") (pin "11") (pinfunction "CRS_DV_11") (pintype "bidirectional"))
      (node (ref "R60") (pin "1") (pinfunction "1_1") (pintype "passive"))
    )
    (net (code "24") (name "Net-(IC8-RBIAS)") (class "Default")
      (node (ref "IC8") (pin "24") (pinfunction "RBIAS_24") (pintype "bidirectional"))
      (node (ref "R63") (pin "2") (pinfunction "2_2") (pintype "passive"))
    )
    (net (code "25") (name "Net-(IC8-RXD0)") (class "Default")
      (node (ref "IC8") (pin "8") (pinfunction "RXD0_8") (pintype "bidirectional"))
      (node (ref "R58") (pin "1") (pinfunction "1_1") (pintype "passive"))
    )
    (net (code "26") (name "Net-(IC8-RXD1)") (class "Default")
      (node (ref "IC8") (pin "7") (pinfunction "RXD1_7") (pintype "bidirectional"))
      (node (ref "R59") (pin "1") (pinfunction "1_1") (pintype "passive"))
    )
    (net (code "27") (name "Net-(IC8-XTAL1)") (class "Default")
      (node (ref "C58") (pin "1") (pinfunction "1_1") (pintype "passive"))
      (node (ref "IC8") (pin "5") (pinfunction "XTAL1_5") (pintype "bidirectional"))
      (node (ref "Q3") (pin "2") (pinfunction "2_2") (pintype "passive"))
      (node (ref "R64") (pin "1") (pinfunction "1_1") (pintype "passive"))
    )
    (net (code "28") (name "Net-(IC8-XTAL2)") (class "Default")
      (node (ref "C59") (pin "1") (pinfunction "1_1") (pintype "passive"))
      (node (ref "IC8") (pin "4") (pinfunction "XTAL2_4") (pintype "bidirectional"))
      (node (ref "Q3") (pin "1") (pinfunction "1_1") (pintype "passive"))
      (node (ref "R64") (pin "2") (pinfunction "2_2") (pintype "passive"))
    )
    (net (code "29") (name "Net-(JP4-D+)") (class "Default")
      (node (ref "JP4") (pin "3") (pinfunction "D+_3") (pintype "bidirectional"))
      (node (ref "R8") (pin "1") (pinfunction "1_1") (pintype "passive"))
    )
    (net (code "30") (name "Net-(JP4-D-)") (class "Default")
      (node (ref "JP4") (pin "2") (pinfunction "D-_2") (pintype "bidirectional"))
      (node (ref "R9") (pin "1") (pinfunction "1_1") (pintype "passive"))
    )
    (net (code "31") (name "Net-(JP4-VCC)") (class "Default")
      (node (ref "JP4") (pin "1") (pinfunction "VCC_1") (pintype "bidirectional"))
      (node (ref "PTC1") (pin "2") (pinfunction "2_2") (pintype "passive"))
    )
    (net (code "32") (name "Net-(LED1-PadA)") (class "Default")
      (node (ref "LED1") (pin "A") (pinfunction "A_A") (pintype "passive"))
      (node (ref "R10") (pin "1") (pinfunction "1_1") (pintype "passive"))
    )
    (net (code "33") (name "Net-(LED2-PadA)") (class "Default")
      (node (ref "LED2") (pin "A") (pinfunction "A_A") (pintype "passive"))
      (node (ref "R11") (pin "1") (pinfunction "1_1") (pintype "passive"))
    )
    (net (code "34") (name "Net-(LED3-PadA)") (class "Default")
      (node (ref "LED3") (pin "A") (pinfunction "A_A") (pintype "passive"))
      (node (ref "R12") (pin "1") (pinfunction "1_1") (pintype "passive"))
    )
    (net (code "35") (name "Net-(LED4-PadA)") (class "Default")
      (node (ref "LED4") (pin "A") (pinfunction "A_A") (pintype "passive"))
      (node (ref "R13") (pin "1") (pinfunction "1_1") (pintype "passive"))
    )
    (net (code "36") (name "Net-(LED5-PadA)") (class "Default")
      (node (ref "LED5") (pin "A") (pinfunction "A_A") (pintype "passive"))
      (node (ref "R14") (pin "1") (pinfunction "1_1") (pintype "passive"))
    )
    (net (code "37") (name "Net-(Q1-D-Pad1)") (class "Default")
      (node (ref "Q1") (pin "1") (pinfunction "D_1") (pintype "passive"))
      (node (ref "Q1") (pin "2") (pinfunction "D_2") (pintype "passive"))
      (node (ref "Q1") (pin "5") (pinfunction "D_5") (pintype "passive"))
      (node (ref "Q1") (pin "6") (pinfunction "D_6") (pintype "passive"))
      (node (ref "R7") (pin "2") (pinfunction "2_2") (pintype "passive"))
    )
    (net (code "38") (name "Net-(R50-Pad2)") (class "Default")
      (node (ref "R50") (pin "2") (pinfunction "2_2") (pintype "passive"))
      (node (ref "RJ1") (pin "Y-") (pinfunction "Y-_Y-") (pintype "bidirectional"))
    )
    (net (code "39") (name "Net-(R61-Pad2)") (class "Default")
      (node (ref "R61") (pin "2") (pinfunction "2_2") (pintype "passive"))
      (node (ref "RJ1") (pin "G-") (pinfunction "G-_G-") (pintype "bidirectional"))
      (node (ref "RJ1") (pin "G--") (pinfunction "G-_G--") (pintype "bidirectional"))
    )
    (net (code "40") (name "P0[0]") (class "Default")
      (node (ref "IC1") (pin "46") (pinfunction "P0[0]/RD1/TXD3/SDA1_46") (pintype "bidirectional"))
      (node (ref "U1") (pin "10") (pinfunction "10_10") (pintype "bidirectional"))
      (node (ref "U1") (pin "23") (pinfunction "23_23") (pintype "bidirectional"))
    )
    (net (code "41") (name "P0[1]") (class "Default")
      (node (ref "IC1") (pin "47") (pinfunction "P0[1]/TD1/RXD3/SCL1_47") (pintype "bidirectional"))
      (node (ref "U1") (pin "48") (pinfunction "48_48") (pintype "bidirectional"))
      (node (ref "U1") (pin "49") (pinfunction "49_49") (pintype "bidirectional"))
    )
    (net (code "42") (name "P0[4]") (class "Default")
      (node (ref "IC1") (pin "81") (pinfunction "P0[4]/I2SRX_CLK/RD2/CAP2[0]_81") (pintype "bidirectional"))
      (node (ref "U1") (pin "8") (pinfunction "8_8") (pintype "bidirectional"))
    )
    (net (code "43") (name "P0[5]") (class "Default")
      (node (ref "IC1") (pin "80") (pinfunction "P0[5]/I2SRX_WS/TD2/CAP2[1]_80") (pintype "bidirectional"))
      (node (ref "U1") (pin "7") (pinfunction "7_7") (pintype "bidirectional"))
    )
    (net (code "44") (name "P0[10]") (class "Default")
      (node (ref "IC1") (pin "48") (pinfunction "P0[10]/TXD2/SDA2/MAT3[0]_48") (pintype "bidirectional"))
      (node (ref "U1") (pin "42") (pinfunction "42_42") (pintype "bidirectional"))
      (node (ref "U1") (pin "46") (pinfunction "46_46") (pintype "bidirectional"))
    )
    (net (code "45") (name "P0[11]") (class "Default")
      (node (ref "IC1") (pin "49") (pinfunction "P0[11]/RXD2/SCL2/MAT3[1]_49") (pintype "bidirectional"))
      (node (ref "U1") (pin "38") (pinfunction "38_38") (pintype "bidirectional"))
    )
    (net (code "46") (name "P0[15]") (class "Default")
      (node (ref "IC1") (pin "62") (pinfunction "P0[15]/TXD1/SCK0/SCK_62") (pintype "bidirectional"))
      (node (ref "U1") (pin "52") (pinfunction "52_52") (pintype "bidirectional"))
    )
    (net (code "47") (name "P0[16]") (class "Default")
      (node (ref "IC1") (pin "63") (pinfunction "P0[16]/RXD1/SSEL0/SSEL_63") (pintype "bidirectional"))
      (node (ref "U1") (pin "44") (pinfunction "44_44") (pintype "bidirectional"))
    )
    (net (code "48") (name "P0[17]") (class "Default")
      (node (ref "IC1") (pin "61") (pinfunction "P0[17]/CTS1/MISO0/MISO_61") (pintype "bidirectional"))
      (node (ref "U1") (pin "50") (pinfunction "50_50") (pintype "bidirectional"))
    )
    (net (code "49") (name "P0[18]") (class "Default")
      (node (ref "IC1") (pin "60") (pinfunction "P0[18]/DCD1/MOSI0/MOSI_60") (pintype "bidirectional"))
      (node (ref "U1") (pin "51") (pinfunction "51_51") (pintype "bidirectional"))
    )
    (net (code "50") (name "P0[19]") (class "Default")
      (node (ref "IC1") (pin "59") (pinfunction "P0[19]/DSR1/SDA1_59") (pintype "bidirectional"))
      (node (ref "U1") (pin "22") (pinfunction "22_22") (pintype "bidirectional"))
    )
    (net (code "51") (name "P0[20]") (class "Default")
      (node (ref "IC1") (pin "58") (pinfunction "P0[20]/DTR1/SCL1_58") (pintype "bidirectional"))
      (node (ref "U1") (pin "24") (pinfunction "24_24") (pintype "bidirectional"))
    )
    (net (code "52") (name "P0[21]") (class "Default")
      (node (ref "IC1") (pin "57") (pinfunction "P0[21]/RI1/RD1_57") (pintype "bidirectional"))
      (node (ref "U1") (pin "26") (pinfunction "26_26") (pintype "bidirectional"))
      (node (ref "U1") (pin "32") (pinfunction "32_32") (pintype "bidirectional"))
    )
    (net (code "53") (name "P0[22]") (class "Default")
      (node (ref "IC1") (pin "56") (pinfunction "P0[22]/RTS1/TD1_56") (pintype "bidirectional"))
      (node (ref "U1") (pin "28") (pinfunction "28_28") (pintype "bidirectional"))
    )
    (net (code "54") (name "P0[23]") (class "Default")
      (node (ref "IC1") (pin "9") (pinfunction "P0[23]/AD0[0]/I2SRX_CLK/CAP3[0]_9") (pintype "bidirectional"))
      (node (ref "U1") (pin "A8") (pinfunction "A8_A8") (pintype "bidirectional"))
    )
    (net (code "55") (name "P0[24]") (class "Default")
      (node (ref "IC1") (pin "8") (pinfunction "P0[24]/AD0[1]/I2SRX_WS/CAP3[1]_8") (pintype "bidirectional"))
      (node (ref "U1") (pin "A1") (pinfunction "A1(TX0)_A1") (pintype "bidirectional"))
    )
    (net (code "56") (name "P0[25]") (class "Default")
      (node (ref "IC1") (pin "7") (pinfunction "P0[25]/AD0[2]/I2SRX_SDA/TXD3_7") (pintype "bidirectional"))
      (node (ref "U1") (pin "A12") (pinfunction "A12_A12") (pintype "bidirectional"))
    )
    (net (code "57") (name "P0[26]") (class "Default")
      (node (ref "IC1") (pin "6") (pinfunction "P0[26]/AD0[3]/AOUT/RXD3_6") (pintype "bidirectional"))
      (node (ref "U1") (pin "A13") (pinfunction "A13_A13") (pintype "bidirectional"))
    )
    (net (code "58") (name "P1[18]") (class "Default")
      (node (ref "IC1") (pin "32") (pinfunction "P1[18]/USB_UP_LED/PWM1[1]/CAP1[0]_32") (pintype "bidirectional"))
      (node (ref "R10") (pin "2") (pinfunction "2_2") (pintype "passive"))
    )
    (net (code "59") (name "P1[19]") (class "Default")
      (node (ref "IC1") (pin "33") (pinfunction "P1[19]/MC0A/USB_PPWR/CAP1[1]_33") (pintype "bidirectional"))
      (node (ref "R11") (pin "2") (pinfunction "2_2") (pintype "passive"))
    )
    (net (code "60") (name "P1[20]") (class "Default")
      (node (ref "IC1") (pin "34") (pinfunction "P1[20]/MCFB0/PWM1[2]/SCK0_34") (pintype "bidirectional"))
      (node (ref "R12") (pin "2") (pinfunction "2_2") (pintype "passive"))
    )
    (net (code "61") (name "P1[21]") (class "Default")
      (node (ref "IC1") (pin "35") (pinfunction "P1[21]/MCABORT/PWM1[3]/SSEL0_35") (pintype "bidirectional"))
      (node (ref "R13") (pin "2") (pinfunction "2_2") (pintype "passive"))
    )
    (net (code "62") (name "P1[22]") (class "Default")
      (node (ref "IC1") (pin "36") (pinfunction "P1[22]/MC0B/USB_PWRD/MAT1[0]_36") (pintype "bidirectional"))
      (node (ref "U1") (pin "A9") (pinfunction "A9_A9") (pintype "bidirectional"))
    )
    (net (code "63") (name "P1[23]") (class "Default")
      (node (ref "IC1") (pin "37") (pinfunction "P1[23]/MCFB1/PWM1[4]/MISO0_37") (pintype "bidirectional"))
      (node (ref "U1") (pin "A10") (pinfunction "A10_A10") (pintype "bidirectional"))
    )
    (net (code "64") (name "P1[24]") (class "Default")
      (node (ref "IC1") (pin "38") (pinfunction "P1[24]/MCFB2/PWM1[5]/MOSI0_38") (pintype "bidirectional"))
      (node (ref "U1") (pin "A2") (pinfunction "A2_A2") (pintype "bidirectional"))
    )
    (net (code "65") (name "P1[25]") (class "Default")
      (node (ref "IC1") (pin "39") (pinfunction "P1[25]/MC1A/MAT1[1]_39") (pintype "bidirectional"))
      (node (ref "U1") (pin "A11") (pinfunction "A11_A11") (pintype "bidirectional"))
    )
    (net (code "66") (name "P1[26]") (class "Default")
      (node (ref "IC1") (pin "40") (pinfunction "P1[26]/MC1B/PWM1[6]/CAP0[0]_40") (pintype "bidirectional"))
      (node (ref "U1") (pin "A6") (pinfunction "A6_A6") (pintype "bidirectional"))
    )
    (net (code "67") (name "P1[27]") (class "Default")
      (node (ref "IC1") (pin "43") (pinfunction "P1[27]/CLKOUT/USB_OVRCR/CAP0[1]_43") (pintype "bidirectional"))
      (node (ref "U1") (pin "A7") (pinfunction "A7_A7") (pintype "bidirectional"))
    )
    (net (code "68") (name "P1[28]") (class "Default")
      (node (ref "IC1") (pin "44") (pinfunction "P1[28]/MC2A/PCAP1[0]/MAT0[0]_44") (pintype "bidirectional"))
      (node (ref "U1") (pin "11") (pinfunction "11_11") (pintype "bidirectional"))
      (node (ref "U1") (pin "25") (pinfunction "25_25") (pintype "bidirectional"))
    )
    (net (code "69") (name "P1[29]") (class "Default")
      (node (ref "IC1") (pin "45") (pinfunction "P1[29]/MC2B/PCAP1[1]/MAT0[1]_45") (pintype "bidirectional"))
      (node (ref "U1") (pin "27") (pinfunction "27_27") (pintype "bidirectional"))
    )
    (net (code "70") (name "P1[30]") (class "Default")
      (node (ref "IC1") (pin "21") (pinfunction "P1[30]/VBUS/AD0[4]_21") (pintype "bidirectional"))
      (node (ref "U1") (pin "A14") (pinfunction "A14_A14") (pintype "bidirectional"))
    )
    (net (code "71") (name "P1[31]") (class "Default")
      (node (ref "IC1") (pin "20") (pinfunction "P1[31]/SCK1/AD0[5]_20") (pintype "bidirectional"))
      (node (ref "U1") (pin "A15") (pinfunction "A15_A15") (pintype "bidirectional"))
    )
    (net (code "72") (name "P2[0]") (class "Default")
      (node (ref "IC1") (pin "75") (pinfunction "P2[0]/PWM1[1]/TXD1_75") (pintype "bidirectional"))
      (node (ref "U1") (pin "6") (pinfunction "6_6") (pintype "bidirectional"))
    )
    (net (code "73") (name "P2[1]") (class "Default")
      (node (ref "IC1") (pin "74") (pinfunction "P2[1]/PWM1[2]/RXD1_74") (pintype "bidirectional"))
      (node (ref "U1") (pin "3") (pinfunction "3_3") (pintype "bidirectional"))
      (node (ref "U1") (pin "5") (pinfunction "5_5") (pintype "bidirectional"))
    )
    (net (code "74") (name "P2[2]") (class "Default")
      (node (ref "IC1") (pin "73") (pinfunction "P2[2]/PWM1[3]/CTS1/TRACEDATA[3]_73") (pintype "bidirectional"))
      (node (ref "U1") (pin "4") (pinfunction "4_4") (pintype "bidirectional"))
    )
    (net (code "75") (name "P2[3]") (class "Default")
      (node (ref "IC1") (pin "70") (pinfunction "P2[3]/PWM1[4]/DCD1/TRACEDATA[2]_70") (pintype "bidirectional"))
      (node (ref "U1") (pin "2") (pinfunction "2_2") (pintype "bidirectional"))
    )
    (net (code "76") (name "P2[4]") (class "Default")
      (node (ref "IC1") (pin "69") (pinfunction "P2[4]/PWM1[5]/DSR1/TRACEDATA[1]_69") (pintype "bidirectional"))
      (node (ref "U1") (pin "13") (pinfunction "13_13") (pintype "bidirectional"))
    )
    (net (code "77") (name "P2[5]") (class "Default")
      (node (ref "IC1") (pin "68") (pinfunction "P2[5]/PWM1[6]/DTR1/TRACEDATA[0]_68") (pintype "bidirectional"))
      (node (ref "U1") (pin "14") (pinfunction "14(TX3)_14") (pintype "bidirectional"))
    )
    (net (code "78") (name "P2[6]") (class "Default")
      (node (ref "IC1") (pin "67") (pinfunction "P2[6]/PCAP1[0]/RI1/TRACECLK_67") (pintype "bidirectional"))
      (node (ref "U1") (pin "15") (pinfunction "15(RX3)_15") (pintype "bidirectional"))
    )
    (net (code "79") (name "P2[7]") (class "Default")
      (node (ref "IC1") (pin "66") (pinfunction "P2[7]/RD2/RTS1_66") (pintype "bidirectional"))
      (node (ref "U1") (pin "18") (pinfunction "18(TX1)_18") (pintype "bidirectional"))
    )
    (net (code "80") (name "P2[8]") (class "Default")
      (node (ref "IC1") (pin "65") (pinfunction "P2[8]/TD2/TXD2_65") (pintype "bidirectional"))
      (node (ref "U1") (pin "19") (pinfunction "19(RX1)_19") (pintype "bidirectional"))
    )
    (net (code "81") (name "P2[10]") (class "Default")
      (node (ref "IC1") (pin "53") (pinfunction "P2[10]/EINT0/NMI_53") (pintype "bidirectional"))
      (node (ref "R5") (pin "1") (pinfunction "1_1") (pintype "passive"))
      (node (ref "S2") (pin "1") (pinfunction "1_1") (pintype "passive"))
      (node (ref "S2") (pin "2") (pinfunction "2_2") (pintype "passive"))
      (node (ref "S4") (pin "1") (pinfunction "1_1") (pintype "passive"))
      (node (ref "S4") (pin "2") (pinfunction "2_2") (pintype "passive"))
      (node (ref "U1") (pin "47") (pinfunction "47_47") (pintype "bidirectional"))
    )
    (net (code "82") (name "P2[11]") (class "Default")
      (node (ref "IC1") (pin "52") (pinfunction "P2[11]/EINT1/I2STX_CLK_52") (pintype "bidirectional"))
      (node (ref "U1") (pin "30") (pinfunction "30_30") (pintype "bidirectional"))
    )
    (net (code "83") (name "P2[12]") (class "Default")
      (node (ref "IC1") (pin "51") (pinfunction "P2[12]/EINT2/I2STX_WS_51") (pintype "bidirectional"))
      (node (ref "U1") (pin "34") (pinfunction "34_34") (pintype "bidirectional"))
      (node (ref "U1") (pin "40") (pinfunction "40_40") (pintype "bidirectional"))
    )
    (net (code "84") (name "P2[13]") (class "Default")
      (node (ref "IC1") (pin "50") (pinfunction "P2[13]/EINT3/I2STX_SDA_50") (pintype "bidirectional"))
      (node (ref "U1") (pin "36") (pinfunction "36_36") (pintype "bidirectional"))
    )
    (net (code "85") (name "P3[25]") (class "Default")
      (node (ref "IC1") (pin "27") (pinfunction "P3[25]/MAT0[0]/PWM1[2]_27") (pintype "bidirectional"))
      (node (ref "U1") (pin "A3") (pinfunction "A3_A3") (pintype "bidirectional"))
    )
    (net (code "86") (name "P3[26]") (class "Default")
      (node (ref "IC1") (pin "26") (pinfunction "P3[26]/STCLK/MAT0[1]/PWM1[3]_26") (pintype "bidirectional"))
      (node (ref "U1") (pin "A0") (pinfunction "A0(RX0)_A0") (pintype "bidirectional"))
    )
    (net (code "87") (name "P4[28]") (class "Default")
      (node (ref "IC1") (pin "82") (pinfunction "P4[28]/RX_MCLK/MAT2[0]/TXD3_82") (pintype "bidirectional"))
      (node (ref "U1") (pin "9") (pinfunction "9_9") (pintype "bidirectional"))
    )
    (net (code "88") (name "P4[29]") (class "Default")
      (node (ref "IC1") (pin "85") (pinfunction "P4[29]/TX_MCLK/MAT2[1]/RXD3_85") (pintype "bidirectional"))
      (node (ref "U1") (pin "12") (pinfunction "12_12") (pintype "bidirectional"))
    )
    (net (code "89") (name "RD+") (class "Default")
      (node (ref "C56") (pin "1") (pinfunction "1_1") (pintype "passive"))
      (node (ref "IC8") (pin "23") (pinfunction "RX+_23") (pintype "bidirectional"))
      (node (ref "R56") (pin "2") (pinfunction "2_2") (pintype "passive"))
      (node (ref "RJ1") (pin "RD+") (pinfunction "RD+_RD+") (pintype "bidirectional"))
    )
    (net (code "90") (name "RD-") (class "Default")
      (node (ref "C57") (pin "1") (pinfunction "1_1") (pintype "passive"))
      (node (ref "IC8") (pin "22") (pinfunction "RX-_22") (pintype "bidirectional"))
      (node (ref "R57") (pin "2") (pinfunction "2_2") (pintype "passive"))
      (node (ref "RJ1") (pin "RD-") (pinfunction "RD-_RD-") (pintype "bidirectional"))
    )
    (net (code "91") (name "RTCK") (class "Default")
      (node (ref "IC1") (pin "100") (pinfunction "RTCK_100") (pintype "bidirectional"))
      (node (ref "JTAG") (pin "7") (pinfunction "7_7") (pintype "passive"))
    )
    (net (code "92") (name "RX_0") (class "Default")
      (node (ref "FTDI") (pin "4") (pinfunction "4_4") (pintype "passive"))
      (node (ref "IC1") (pin "99") (pinfunction "P0[3]/RXD0/AD0[6]_99") (pintype "bidirectional"))
      (node (ref "U1") (pin "0") (pinfunction "0(RX0)_0") (pintype "bidirectional"))
    )
    (net (code "93") (name "SCL") (class "Default")
      (node (ref "IC1") (pin "24") (pinfunction "P0[28]/SCL0/USB_SCL_24") (pintype "bidirectional"))
      (node (ref "U1") (pin "21") (pinfunction "21(SCL)_21") (pintype "bidirectional"))
      (node (ref "U1") (pin "SCL1") (pinfunction "SCL_SCL1") (pintype "bidirectional"))
    )
    (net (code "94") (name "SDA") (class "Default")
      (node (ref "IC1") (pin "25") (pinfunction "P0[27]/SDA0/USB_SDA_25") (pintype "bidirectional"))
      (node (ref "U1") (pin "20") (pinfunction "20(SDA)_20") (pintype "bidirectional"))
      (node (ref "U1") (pin "SDA1") (pinfunction "SDA_SDA1") (pintype "bidirectional"))
    )
    (net (code "95") (name "SD_CS") (class "Default")
      (node (ref "IC1") (pin "79") (pinfunction "P0[6]/I2SRX_SDA/SSEL1/MAT2[0]_79") (pintype "bidirectional"))
      (node (ref "X1") (pin "2") (pinfunction "D3_2") (pintype "bidirectional"))
    )
    (net (code "96") (name "SD_MISO") (class "Default")
      (node (ref "IC1") (pin "77") (pinfunction "P0[8]/I2STX_WS/MISO1/MAT2[2]_77") (pintype "bidirectional"))
      (node (ref "U1") (pin "MISO") (pinfunction "MISO_MISO") (pintype "bidirectional"))
      (node (ref "X1") (pin "7") (pinfunction "D0_7") (pintype "bidirectional"))
    )
    (net (code "97") (name "SD_MOSI") (class "Default")
      (node (ref "IC1") (pin "76") (pinfunction "P0[9]/I2STX_SDA/MOSI1/MAT2[3]_76") (pintype "bidirectional"))
      (node (ref "U1") (pin "MOSI") (pinfunction "MOSI_MOSI") (pintype "bidirectional"))
      (node (ref "X1") (pin "3") (pinfunction "CMD_3") (pintype "bidirectional"))
    )
    (net (code "98") (name "SD_SCK") (class "Default")
      (node (ref "IC1") (pin "78") (pinfunction "P0[7]/I2STX_CLK/SCK1/MAT2[1]_78") (pintype "bidirectional"))
      (node (ref "U1") (pin "SCK") (pinfunction "SCK_SCK") (pintype "bidirectional"))
      (node (ref "X1") (pin "5") (pinfunction "CLK_5") (pintype "input"))
    )
    (net (code "99") (name "TCK-SWDCLK") (class "Default")
      (node (ref "IC1") (pin "5") (pinfunction "TCK/SWDCLK_5") (pintype "bidirectional"))
      (node (ref "JTAG") (pin "4") (pinfunction "4_4") (pintype "passive"))
    )
    (net (code "100") (name "TD+") (class "Default")
      (node (ref "C54") (pin "1") (pinfunction "1_1") (pintype "passive"))
      (node (ref "IC8") (pin "21") (pinfunction "TX+_21") (pintype "bidirectional"))
      (node (ref "R54") (pin "2") (pinfunction "2_2") (pintype "passive"))
      (node (ref "RJ1") (pin "TD+") (pinfunction "TD+_TD+") (pintype "bidirectional"))
    )
    (net (code "101") (name "TD-") (class "Default")
      (node (ref "C55") (pin "1") (pinfunction "1_1") (pintype "passive"))
      (node (ref "IC8") (pin "20") (pinfunction "TX-_20") (pintype "bidirectional"))
      (node (ref "R55") (pin "2") (pinfunction "2_2") (pintype "passive"))
      (node (ref "RJ1") (pin "TD-") (pinfunction "TD-_TD-") (pintype "bidirectional"))
    )
    (net (code "102") (name "TDI") (class "Default")
      (node (ref "IC1") (pin "2") (pinfunction "TDI_2") (pintype "bidirectional"))
      (node (ref "JTAG") (pin "8") (pinfunction "8_8") (pintype "passive"))
    )
    (net (code "103") (name "TDO-SWO") (class "Default")
      (node (ref "IC1") (pin "1") (pinfunction "TDO/SWO_1") (pintype "bidirectional"))
      (node (ref "JTAG") (pin "6") (pinfunction "6_6") (pintype "passive"))
    )
    (net (code "104") (name "TMS-SWDIO") (class "Default")
      (node (ref "IC1") (pin "3") (pinfunction "TMS/SWDIO_3") (pintype "bidirectional"))
      (node (ref "JTAG") (pin "2") (pinfunction "2_2") (pintype "passive"))
    )
    (net (code "105") (name "TX_0") (class "Default")
      (node (ref "FTDI") (pin "5") (pinfunction "5_5") (pintype "passive"))
      (node (ref "IC1") (pin "98") (pinfunction "P0[2]/TXD0/AD0[7]_98") (pintype "bidirectional"))
      (node (ref "U1") (pin "1") (pinfunction "1(TX0)_1") (pintype "bidirectional"))
    )
    (net (code "106") (name "USB_CONNECT") (class "Default")
      (node (ref "IC1") (pin "64") (pinfunction "P2[9]/USB_CONNECT/RXD2_64") (pintype "bidirectional"))
      (node (ref "Q1") (pin "3") (pinfunction "G_3") (pintype "passive"))
    )
    (net (code "107") (name "USB_N") (class "Default")
      (node (ref "C4") (pin "2") (pinfunction "2_2") (pintype "passive"))
      (node (ref "IC1") (pin "30") (pinfunction "P0[30]/USB_D-_30") (pintype "bidirectional"))
      (node (ref "R9") (pin "2") (pinfunction "2_2") (pintype "passive"))
    )
    (net (code "108") (name "USB_P") (class "Default")
      (node (ref "C5") (pin "2") (pinfunction "2_2") (pintype "passive"))
      (node (ref "IC1") (pin "29") (pinfunction "P0[29]/USB_D+_29") (pintype "bidirectional"))
      (node (ref "R7") (pin "1") (pinfunction "1_1") (pintype "passive"))
      (node (ref "R8") (pin "2") (pinfunction "2_2") (pintype "passive"))
    )
    (net (code "109") (name "VUSB") (class "Default")
      (node (ref "D1") (pin "A") (pinfunction "A_A") (pintype "passive"))
      (node (ref "PTC1") (pin "1") (pinfunction "1_1") (pintype "passive"))
    )
    (net (code "110") (name "unconnected-(FTDI-Pad2)") (class "Default")
      (node (ref "FTDI") (pin "2") (pinfunction "2_2") (pintype "passive"))
    )
    (net (code "111") (name "unconnected-(FTDI-Pad3)") (class "Default")
      (node (ref "FTDI") (pin "3") (pinfunction "3_3") (pintype "passive"))
    )
    (net (code "112") (name "unconnected-(FTDI-Pad6)") (class "Default")
      (node (ref "FTDI") (pin "6") (pinfunction "6_6") (pintype "passive"))
    )
    (net (code "113") (name "unconnected-(IC1-N.C.-Pad13)") (class "Default")
      (node (ref "IC1") (pin "13") (pinfunction "N.C._13") (pintype "bidirectional"))
    )
    (net (code "114") (name "unconnected-(IC1-RTCX1-Pad16)") (class "Default")
      (node (ref "IC1") (pin "16") (pinfunction "RTCX1_16") (pintype "bidirectional"))
    )
    (net (code "115") (name "unconnected-(IC1-RTCX2-Pad18)") (class "Default")
      (node (ref "IC1") (pin "18") (pinfunction "RTCX2_18") (pintype "bidirectional"))
    )
    (net (code "116") (name "unconnected-(IC1-TRST-Pad4)") (class "Default")
      (node (ref "IC1") (pin "4") (pinfunction "TRST_4") (pintype "bidirectional"))
    )
    (net (code "117") (name "unconnected-(IC7-NC-Pad1)") (class "Default")
      (node (ref "IC7") (pin "1") (pinfunction "NC_1") (pintype "no_connect"))
    )
    (net (code "118") (name "unconnected-(JP4-ID-Pad4)") (class "Default")
      (node (ref "JP4") (pin "4") (pinfunction "ID_4") (pintype "bidirectional"))
    )
    (net (code "119") (name "unconnected-(JP4-SHIELD-Pad7)") (class "Default")
      (node (ref "JP4") (pin "7") (pinfunction "SHIELD_7") (pintype "bidirectional"))
    )
    (net (code "120") (name "unconnected-(JP4-SHIELD-Pad11)") (class "Default")
      (node (ref "JP4") (pin "11") (pinfunction "SHIELD_11") (pintype "bidirectional"))
    )
    (net (code "121") (name "unconnected-(JP4-SHIELD-Pad12)") (class "Default")
      (node (ref "JP4") (pin "12") (pinfunction "SHIELD_12") (pintype "bidirectional"))
    )
    (net (code "122") (name "unconnected-(JP4-SHIELD-Pad17)") (class "Default")
      (node (ref "JP4") (pin "17") (pinfunction "SHIELD_17") (pintype "bidirectional"))
    )
    (net (code "123") (name "unconnected-(RJ1-PadNC)") (class "Default")
      (node (ref "RJ1") (pin "NC") (pinfunction "NC_NC") (pintype "bidirectional"))
    )
    (net (code "124") (name "unconnected-(U1-16(TX2)-Pad16)") (class "Default")
      (node (ref "U1") (pin "16") (pinfunction "16(TX2)_16") (pintype "bidirectional"))
    )
    (net (code "125") (name "unconnected-(U1-17(RX2)-Pad17)") (class "Default")
      (node (ref "U1") (pin "17") (pinfunction "17(RX2)_17") (pintype "bidirectional"))
    )
    (net (code "126") (name "unconnected-(U1-Pad29)") (class "Default")
      (node (ref "U1") (pin "29") (pinfunction "29_29") (pintype "bidirectional"))
    )
    (net (code "127") (name "unconnected-(U1-Pad31)") (class "Default")
      (node (ref "U1") (pin "31") (pinfunction "31_31") (pintype "bidirectional"))
    )
    (net (code "128") (name "unconnected-(U1-Pad33)") (class "Default")
      (node (ref "U1") (pin "33") (pinfunction "33_33") (pintype "bidirectional"))
    )
    (net (code "129") (name "unconnected-(U1-Pad35)") (class "Default")
      (node (ref "U1") (pin "35") (pinfunction "35_35") (pintype "bidirectional"))
    )
    (net (code "130") (name "unconnected-(U1-Pad37)") (class "Default")
      (node (ref "U1") (pin "37") (pinfunction "37_37") (pintype "bidirectional"))
    )
    (net (code "131") (name "unconnected-(U1-Pad39)") (class "Default")
      (node (ref "U1") (pin "39") (pinfunction "39_39") (pintype "bidirectional"))
    )
    (net (code "132") (name "unconnected-(U1-Pad41)") (class "Default")
      (node (ref "U1") (pin "41") (pinfunction "41_41") (pintype "bidirectional"))
    )
    (net (code "133") (name "unconnected-(U1-Pad43)") (class "Default")
      (node (ref "U1") (pin "43") (pinfunction "43_43") (pintype "bidirectional"))
    )
    (net (code "134") (name "unconnected-(U1-Pad45)") (class "Default")
      (node (ref "U1") (pin "45") (pinfunction "45_45") (pintype "bidirectional"))
    )
    (net (code "135") (name "unconnected-(U1-Pad53)") (class "Default")
      (node (ref "U1") (pin "53") (pinfunction "53_53") (pintype "bidirectional"))
    )
    (net (code "136") (name "unconnected-(U1-PadA4)") (class "Default")
      (node (ref "U1") (pin "A4") (pinfunction "A4_A4") (pintype "bidirectional"))
    )
    (net (code "137") (name "unconnected-(U1-PadA5)") (class "Default")
      (node (ref "U1") (pin "A5") (pinfunction "A5_A5") (pintype "bidirectional"))
    )
    (net (code "138") (name "unconnected-(U1-PadAREF)") (class "Default")
      (node (ref "U1") (pin "AREF") (pinfunction "AREF_AREF") (pintype "bidirectional"))
    )
    (net (code "139") (name "unconnected-(U1-PadVIN)") (class "Default")
      (node (ref "U1") (pin "VIN") (pinfunction "VIN_VIN") (pintype "bidirectional"))
    )
    (net (code "140") (name "unconnected-(X1-D1-Pad8)") (class "Default")
      (node (ref "X1") (pin "8") (pinfunction "D1_8") (pintype "bidirectional"))
    )
    (net (code "141") (name "unconnected-(X1-D2-Pad1)") (class "Default")
      (node (ref "X1") (pin "1") (pinfunction "D2_1") (pintype "bidirectional"))
    )
    (net (code "142") (name "~{RSTOUT}") (class "Default")
      (node (ref "IC1") (pin "14") (pinfunction "RSTOUT_14") (pintype "bidirectional"))
      (node (ref "IC8") (pin "15") (pinfunction "NRST_15") (pintype "bidirectional"))
    )
    (net (code "143") (name "~{RST}") (class "Default")
      (node (ref "IC1") (pin "17") (pinfunction "RESET_17") (pintype "bidirectional"))
      (node (ref "JTAG") (pin "10") (pinfunction "10_10") (pintype "passive"))
      (node (ref "R4") (pin "1") (pinfunction "1_1") (pintype "passive"))
      (node (ref "S1") (pin "1") (pinfunction "1_1") (pintype "passive"))
      (node (ref "S1") (pin "2") (pinfunction "2_2") (pintype "passive"))
      (node (ref "S3") (pin "1") (pinfunction "1_1") (pintype "passive"))
      (node (ref "S3") (pin "2") (pinfunction "2_2") (pintype "passive"))
      (node (ref "U1") (pin "RESET") (pinfunction "RESET_RESET") (pintype "bidirectional"))
      (node (ref "U1") (pin "RST") (pinfunction "RESET_RST") (pintype "bidirectional"))
    )
  )
)
